# CAN_Transceiver.net
KiCad netlist of a schematic drawn in Altium Designer
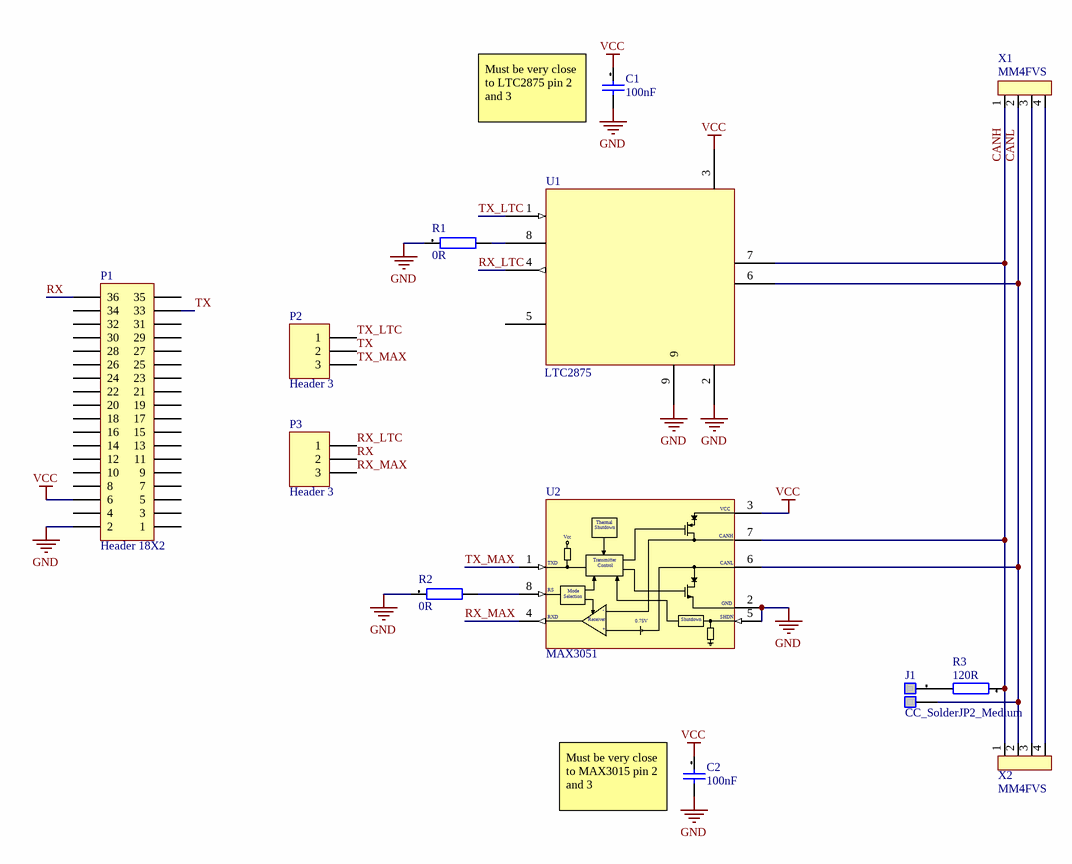
[diagram p0: CAN_Transceiver.SchDoc]

(export (version "E")
  (design (tool "Eeschema 10.0.6"))
  (components
    (comp (ref "C1")
      (value "100nF")
      (footprint "CAPC1005X05L")
      (description "Capacitor")
      (fields (field (name "MANUFACTURER") "Kemet") (field (name "VOLTAGE") "16"))
      (libsource (lib "LSRO1Altium") (part "CAP-NP"))
    )
    (comp (ref "C2")
      (value "100nF")
      (footprint "CAPC1005X05L")
      (description "Capacitor")
      (fields (field (name "MANUFACTURER") "Kemet") (field (name "VOLTAGE") "16"))
      (libsource (lib "LSRO1Altium") (part "CAP-NP"))
    )
    (comp (ref "J1")
      (value "CC_SolderJP2_Medium")
      (footprint "CC_SolderJP_M")
      (description "Medium Solder Jumper 2 leads")
      (libsource (lib "LSRO1Altium") (part "SolderJP2"))
    )
    (comp (ref "P1")
      (value "Header 18X2")
      (footprint "HDR2X18")
      (description "Header, 18-Pin, Dual row")
      (fields (field (name "PUBLISHER") "Altium Limited"))
      (libsource (lib "Miscellaneous Connectors") (part "Header 18X2"))
    )
    (comp (ref "P2")
      (value "Header 3")
      (footprint "HDR1X3")
      (description "Header, 3-Pin")
      (fields (field (name "PUBLISHER") "Altium Limited"))
      (libsource (lib "Miscellaneous Connectors") (part "Header 3"))
    )
    (comp (ref "P3")
      (value "Header 3")
      (footprint "HDR1X3")
      (description "Header, 3-Pin")
      (fields (field (name "PUBLISHER") "Altium Limited"))
      (libsource (lib "Miscellaneous Connectors") (part "Header 3"))
    )
    (comp (ref "R1")
      (value "0R")
      (footprint "RESC1608X06L")
      (description "Resistor")
      (fields (field (name "TOLERANCE") "+/-1") (field (name "MANUFACTURER") "Vishay"))
      (libsource (lib "LSRO1Altium") (part "RES"))
    )
    (comp (ref "R2")
      (value "0R")
      (footprint "RESC1608X06L")
      (description "Resistor")
      (fields (field (name "TOLERANCE") "+/-1") (field (name "MANUFACTURER") "Vishay"))
      (libsource (lib "LSRO1Altium") (part "RES"))
    )
    (comp (ref "R3")
      (value "120R")
      (footprint "RESC1608X06L")
      (description "Resistor")
      (fields (field (name "TOLERANCE") "+/-1") (field (name "MANUFACTURER") "Vishay"))
      (libsource (lib "LSRO1Altium") (part "RES"))
    )
    (comp (ref "U1") (value "LTC2875") (libsource (lib "LTC2875") (part "LTC2875")))
    (comp (ref "U2") (value "MAX3051") (footprint "SOT-23, 8L") (libsource (lib "ICs") (part "MAX3051")))
    (comp (ref "X1")
      (value "MM4FVS")
      (footprint "TYCO_7-188275-4")
      (description "Micro-Match 4 pins Female on board Vertical Smd connector")
      (fields (field (name "MANUFACTURER") "Tyco"))
      (libsource (lib "LSRO1Altium") (part "Con1x4"))
    )
    (comp (ref "X2")
      (value "MM4FVS")
      (footprint "TYCO_7-188275-4")
      (description "Micro-Match 4 pins Female on board Vertical Smd connector")
      (fields (field (name "MANUFACTURER") "Tyco"))
      (libsource (lib "") (part "Con1x4_1"))
    )
  )
  (nets
    (net (code "1") (name "/CANH") (class "Default")
      (node (ref "R3") (pin "1") (pinfunction "1_1") (pintype "passive"))
      (node (ref "U1") (pin "7") (pintype "passive"))
      (node (ref "U2") (pin "7") (pinfunction "CANH_7") (pintype "passive"))
      (node (ref "X1") (pin "1") (pinfunction "1_1") (pintype "passive"))
      (node (ref "X2") (pin "1") (pinfunction "1_1") (pintype "passive"))
    )
    (net (code "2") (name "/CANL") (class "Default")
      (node (ref "J1") (pin "2") (pintype "passive"))
      (node (ref "U1") (pin "6") (pintype "passive"))
      (node (ref "U2") (pin "6") (pinfunction "CANL_6") (pintype "passive"))
      (node (ref "X1") (pin "2") (pinfunction "2_2") (pintype "passive"))
      (node (ref "X2") (pin "2") (pinfunction "2_2") (pintype "passive"))
    )
    (net (code "3") (name "/RX") (class "Default")
      (node (ref "P1") (pin "36") (pinfunction "36_36") (pintype "passive"))
      (node (ref "P3") (pin "2") (pinfunction "2_2") (pintype "passive"))
    )
    (net (code "4") (name "/RX_LTC") (class "Default")
      (node (ref "P3") (pin "1") (pinfunction "1_1") (pintype "passive"))
      (node (ref "U1") (pin "4") (pintype "output"))
    )
    (net (code "5") (name "/RX_MAX") (class "Default")
      (node (ref "P3") (pin "3") (pinfunction "3_3") (pintype "passive"))
      (node (ref "U2") (pin "4") (pinfunction "RXD_4") (pintype "output"))
    )
    (net (code "6") (name "/TX") (class "Default")
      (node (ref "P1") (pin "33") (pinfunction "33_33") (pintype "passive"))
      (node (ref "P2") (pin "2") (pinfunction "2_2") (pintype "passive"))
    )
    (net (code "7") (name "/TX_LTC") (class "Default")
      (node (ref "P2") (pin "1") (pinfunction "1_1") (pintype "passive"))
      (node (ref "U1") (pin "1") (pintype "input"))
    )
    (net (code "8") (name "/TX_MAX") (class "Default")
      (node (ref "P2") (pin "3") (pinfunction "3_3") (pintype "passive"))
      (node (ref "U2") (pin "1") (pinfunction "TXD_1") (pintype "input"))
    )
    (net (code "9") (name "GND") (class "Default")
      (node (ref "C1") (pin "2") (pinfunction "2_2") (pintype "passive"))
      (node (ref "C2") (pin "2") (pinfunction "2_2") (pintype "passive"))
      (node (ref "P1") (pin "2") (pinfunction "2_2") (pintype "passive"))
      (node (ref "R1") (pin "1") (pinfunction "1_1") (pintype "passive"))
      (node (ref "R2") (pin "1") (pinfunction "1_1") (pintype "passive"))
      (node (ref "U1") (pin "2") (pintype "passive"))
      (node (ref "U1") (pin "9") (pinfunction "9_9") (pintype "passive"))
      (node (ref "U2") (pin "2") (pinfunction "GND_2") (pintype "power_in"))
      (node (ref "U2") (pin "5") (pinfunction "SHDN_5") (pintype "input"))
    )
    (net (code "10") (name "Net-(J1-Pad1)") (class "Default")
      (node (ref "J1") (pin "1") (pintype "passive"))
      (node (ref "R3") (pin "2") (pinfunction "2_2") (pintype "passive"))
    )
    (net (code "11") (name "Net-(R1-Pad2)") (class "Default")
      (node (ref "R1") (pin "2") (pinfunction "2_2") (pintype "passive"))
      (node (ref "U1") (pin "8") (pintype "passive"))
    )
    (net (code "12") (name "Net-(U2-RS)") (class "Default")
      (node (ref "R2") (pin "2") (pinfunction "2_2") (pintype "passive"))
      (node (ref "U2") (pin "8") (pinfunction "RS_8") (pintype "input"))
    )
    (net (code "13") (name "Net-(X1-Pad3)") (class "Default")
      (node (ref "X1") (pin "3") (pinfunction "3_3") (pintype "passive"))
      (node (ref "X2") (pin "3") (pinfunction "3_3") (pintype "passive"))
    )
    (net (code "14") (name "Net-(X1-Pad4)") (class "Default")
      (node (ref "X1") (pin "4") (pinfunction "4_4") (pintype "passive"))
      (node (ref "X2") (pin "4") (pinfunction "4_4") (pintype "passive"))
    )
    (net (code "15") (name "VCC") (class "Default")
      (node (ref "C1") (pin "1") (pinfunction "1_1") (pintype "passive"))
      (node (ref "C2") (pin "1") (pinfunction "1_1") (pintype "passive"))
      (node (ref "P1") (pin "6") (pinfunction "6_6") (pintype "passive"))
      (node (ref "U1") (pin "3") (pintype "passive"))
      (node (ref "U2") (pin "3") (pinfunction "VCC_3") (pintype "power_in"))
    )
    (net (code "16") (name "unconnected-(P1-Pad1)") (class "Default")
      (node (ref "P1") (pin "1") (pinfunction "1_1") (pintype "passive"))
    )
    (net (code "17") (name "unconnected-(P1-Pad3)") (class "Default")
      (node (ref "P1") (pin "3") (pinfunction "3_3") (pintype "passive"))
    )
    (net (code "18") (name "unconnected-(P1-Pad4)") (class "Default")
      (node (ref "P1") (pin "4") (pinfunction "4_4") (pintype "passive"))
    )
    (net (code "19") (name "unconnected-(P1-Pad5)") (class "Default")
      (node (ref "P1") (pin "5") (pinfunction "5_5") (pintype "passive"))
    )
    (net (code "20") (name "unconnected-(P1-Pad7)") (class "Default")
      (node (ref "P1") (pin "7") (pinfunction "7_7") (pintype "passive"))
    )
    (net (code "21") (name "unconnected-(P1-Pad8)") (class "Default")
      (node (ref "P1") (pin "8") (pinfunction "8_8") (pintype "passive"))
    )
    (net (code "22") (name "unconnected-(P1-Pad9)") (class "Default")
      (node (ref "P1") (pin "9") (pinfunction "9_9") (pintype "passive"))
    )
    (net (code "23") (name "unconnected-(P1-Pad10)") (class "Default")
      (node (ref "P1") (pin "10") (pinfunction "10_10") (pintype "passive"))
    )
    (net (code "24") (name "unconnected-(P1-Pad11)") (class "Default")
      (node (ref "P1") (pin "11") (pinfunction "11_11") (pintype "passive"))
    )
    (net (code "25") (name "unconnected-(P1-Pad12)") (class "Default")
      (node (ref "P1") (pin "12") (pinfunction "12_12") (pintype "passive"))
    )
    (net (code "26") (name "unconnected-(P1-Pad13)") (class "Default")
      (node (ref "P1") (pin "13") (pinfunction "13_13") (pintype "passive"))
    )
    (net (code "27") (name "unconnected-(P1-Pad14)") (class "Default")
      (node (ref "P1") (pin "14") (pinfunction "14_14") (pintype "passive"))
    )
    (net (code "28") (name "unconnected-(P1-Pad15)") (class "Default")
      (node (ref "P1") (pin "15") (pinfunction "15_15") (pintype "passive"))
    )
    (net (code "29") (name "unconnected-(P1-Pad16)") (class "Default")
      (node (ref "P1") (pin "16") (pinfunction "16_16") (pintype "passive"))
    )
    (net (code "30") (name "unconnected-(P1-Pad17)") (class "Default")
      (node (ref "P1") (pin "17") (pinfunction "17_17") (pintype "passive"))
    )
    (net (code "31") (name "unconnected-(P1-Pad18)") (class "Default")
      (node (ref "P1") (pin "18") (pinfunction "18_18") (pintype "passive"))
    )
    (net (code "32") (name "unconnected-(P1-Pad19)") (class "Default")
      (node (ref "P1") (pin "19") (pinfunction "19_19") (pintype "passive"))
    )
    (net (code "33") (name "unconnected-(P1-Pad20)") (class "Default")
      (node (ref "P1") (pin "20") (pinfunction "20_20") (pintype "passive"))
    )
    (net (code "34") (name "unconnected-(P1-Pad21)") (class "Default")
      (node (ref "P1") (pin "21") (pinfunction "21_21") (pintype "passive"))
    )
    (net (code "35") (name "unconnected-(P1-Pad22)") (class "Default")
      (node (ref "P1") (pin "22") (pinfunction "22_22") (pintype "passive"))
    )
    (net (code "36") (name "unconnected-(P1-Pad23)") (class "Default")
      (node (ref "P1") (pin "23") (pinfunction "23_23") (pintype "passive"))
    )
    (net (code "37") (name "unconnected-(P1-Pad24)") (class "Default")
      (node (ref "P1") (pin "24") (pinfunction "24_24") (pintype "passive"))
    )
    (net (code "38") (name "unconnected-(P1-Pad25)") (class "Default")
      (node (ref "P1") (pin "25") (pinfunction "25_25") (pintype "passive"))
    )
    (net (code "39") (name "unconnected-(P1-Pad26)") (class "Default")
      (node (ref "P1") (pin "26") (pinfunction "26_26") (pintype "passive"))
    )
    (net (code "40") (name "unconnected-(P1-Pad27)") (class "Default")
      (node (ref "P1") (pin "27") (pinfunction "27_27") (pintype "passive"))
    )
    (net (code "41") (name "unconnected-(P1-Pad28)") (class "Default")
      (node (ref "P1") (pin "28") (pinfunction "28_28") (pintype "passive"))
    )
    (net (code "42") (name "unconnected-(P1-Pad29)") (class "Default")
      (node (ref "P1") (pin "29") (pinfunction "29_29") (pintype "passive"))
    )
    (net (code "43") (name "unconnected-(P1-Pad30)") (class "Default")
      (node (ref "P1") (pin "30") (pinfunction "30_30") (pintype "passive"))
    )
    (net (code "44") (name "unconnected-(P1-Pad31)") (class "Default")
      (node (ref "P1") (pin "31") (pinfunction "31_31") (pintype "passive"))
    )
    (net (code "45") (name "unconnected-(P1-Pad32)") (class "Default")
      (node (ref "P1") (pin "32") (pinfunction "32_32") (pintype "passive"))
    )
    (net (code "46") (name "unconnected-(P1-Pad34)") (class "Default")
      (node (ref "P1") (pin "34") (pinfunction "34_34") (pintype "passive"))
    )
    (net (code "47") (name "unconnected-(P1-Pad35)") (class "Default")
      (node (ref "P1") (pin "35") (pinfunction "35_35") (pintype "passive"))
    )
    (net (code "48") (name "unconnected-(U1-Pad5)") (class "Default")
      (node (ref "U1") (pin "5") (pintype "passive"))
    )
  )
)
